# Codeshelf-0013_v00.net
KiCad netlist of a schematic drawn in EAGLE
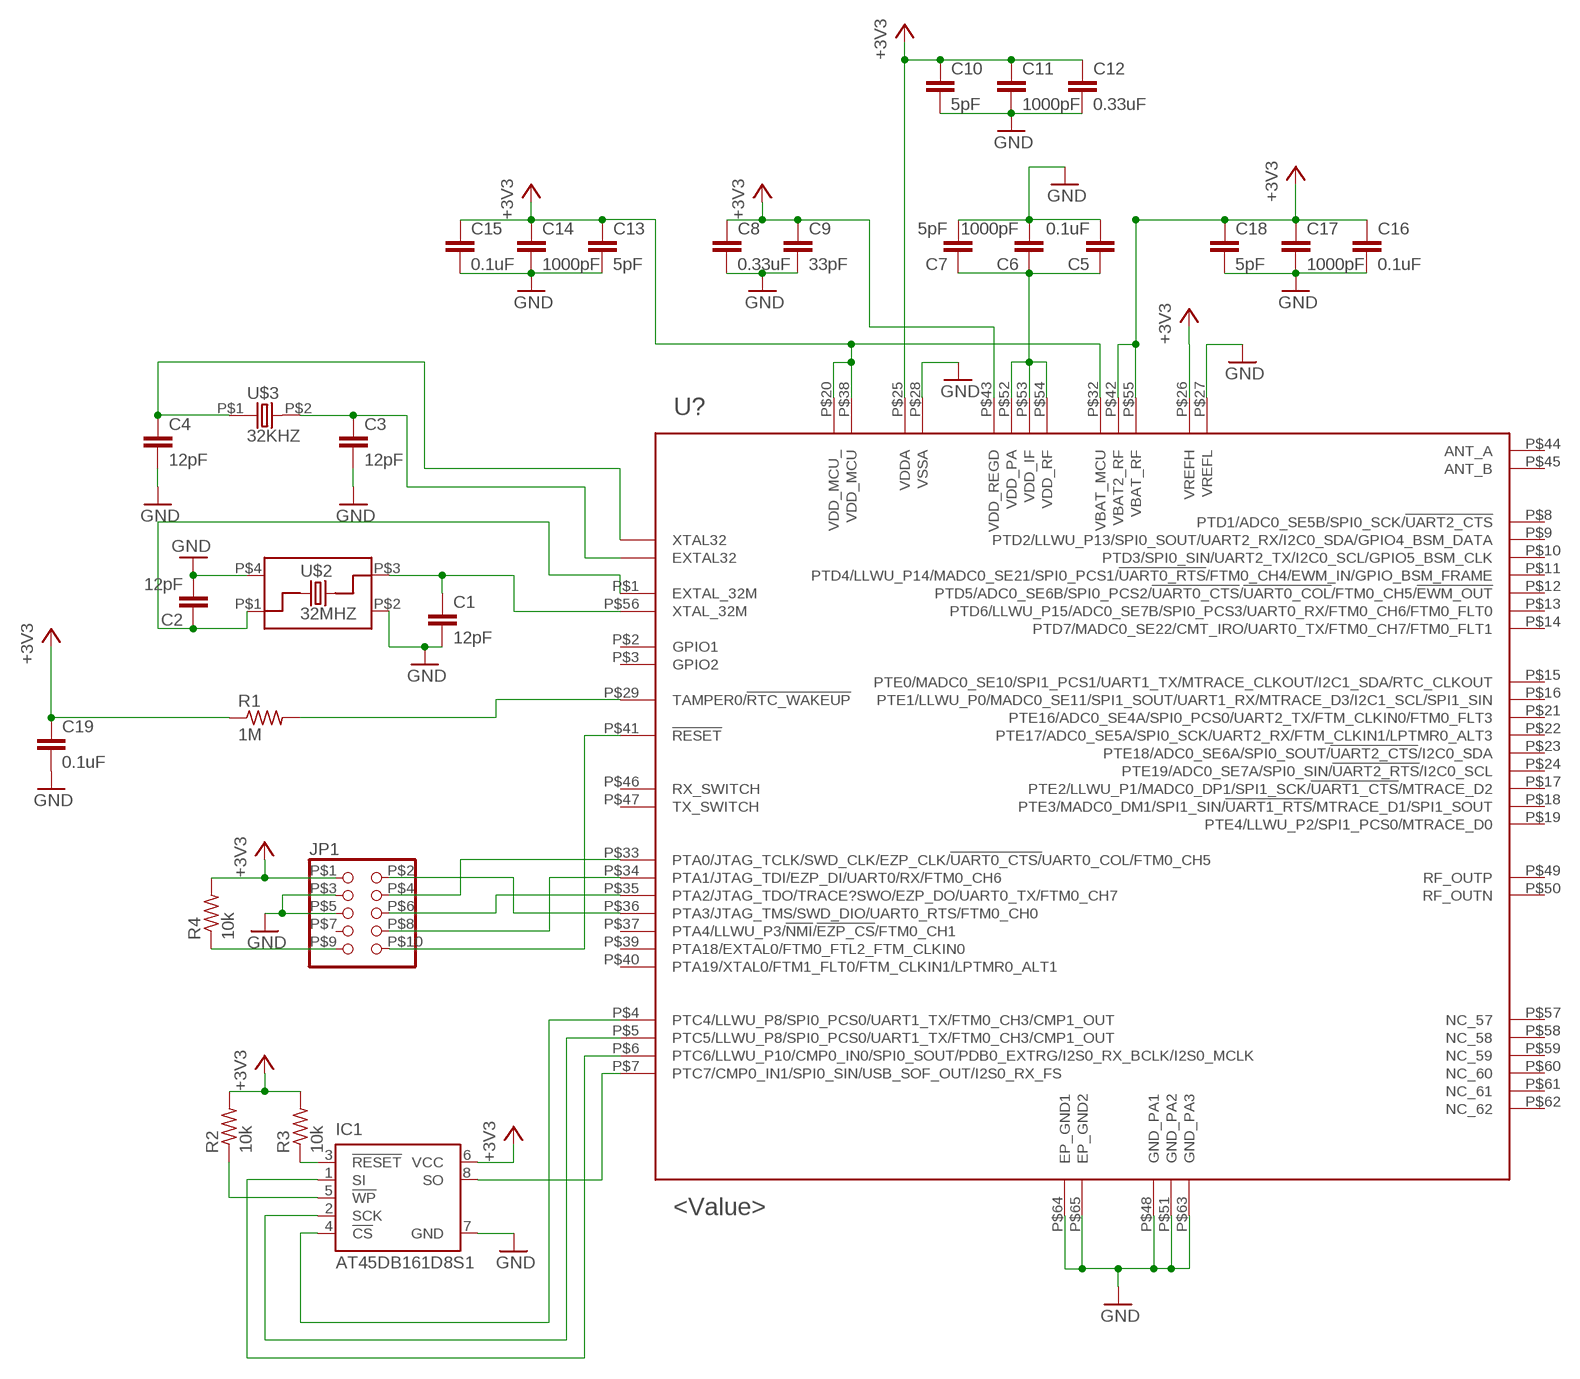
[diagram p0: schematic, sheet 1]

(export (version "E")
  (design (tool "Eeschema 10.0.6"))
  (components
    (comp (ref "C1")
      (value "12pF")
      (footprint "eagle-import:C0402")
      (libsource (lib "eagle-import") (part "RF-C0402"))
    )
    (comp (ref "C2")
      (value "12pF")
      (footprint "eagle-import:C0402")
      (libsource (lib "eagle-import") (part "RF-C0402"))
    )
    (comp (ref "C3")
      (value "12pF")
      (footprint "eagle-import:C0402")
      (libsource (lib "eagle-import") (part "RF-C0402"))
    )
    (comp (ref "C4")
      (value "12pF")
      (footprint "eagle-import:C0402")
      (libsource (lib "eagle-import") (part "RF-C0402"))
    )
    (comp (ref "C5")
      (value "0.1uF")
      (footprint "eagle-import:C0402")
      (libsource (lib "eagle-import") (part "RF-C0402"))
    )
    (comp (ref "C6")
      (value "1000pF")
      (footprint "eagle-import:C0402")
      (libsource (lib "eagle-import") (part "RF-C0402"))
    )
    (comp (ref "C7")
      (value "5pF")
      (footprint "eagle-import:C0402")
      (libsource (lib "eagle-import") (part "RF-C0402"))
    )
    (comp (ref "C8")
      (value "0.33uF")
      (footprint "eagle-import:C0402")
      (libsource (lib "eagle-import") (part "RF-C0402"))
    )
    (comp (ref "C9")
      (value "33pF")
      (footprint "eagle-import:C0402")
      (libsource (lib "eagle-import") (part "RF-C0402"))
    )
    (comp (ref "C10")
      (value "5pF")
      (footprint "eagle-import:C0402")
      (libsource (lib "eagle-import") (part "RF-C0402"))
    )
    (comp (ref "C11")
      (value "1000pF")
      (footprint "eagle-import:C0402")
      (libsource (lib "eagle-import") (part "RF-C0402"))
    )
    (comp (ref "C12")
      (value "0.33uF")
      (footprint "eagle-import:C0402")
      (libsource (lib "eagle-import") (part "RF-C0402"))
    )
    (comp (ref "C13")
      (value "5pF")
      (footprint "eagle-import:C0402")
      (libsource (lib "eagle-import") (part "RF-C0402"))
    )
    (comp (ref "C14")
      (value "1000pF")
      (footprint "eagle-import:C0402")
      (libsource (lib "eagle-import") (part "RF-C0402"))
    )
    (comp (ref "C15")
      (value "0.1uF")
      (footprint "eagle-import:C0402")
      (libsource (lib "eagle-import") (part "RF-C0402"))
    )
    (comp (ref "C16")
      (value "0.1uF")
      (footprint "eagle-import:C0402")
      (libsource (lib "eagle-import") (part "RF-C0402"))
    )
    (comp (ref "C17")
      (value "1000pF")
      (footprint "eagle-import:C0402")
      (libsource (lib "eagle-import") (part "RF-C0402"))
    )
    (comp (ref "C18")
      (value "5pF")
      (footprint "eagle-import:C0402")
      (libsource (lib "eagle-import") (part "RF-C0402"))
    )
    (comp (ref "C19")
      (value "0.1uF")
      (footprint "eagle-import:C0402")
      (libsource (lib "eagle-import") (part "RF-C0402"))
    )
    (comp (ref "IC1")
      (value "AT45DB161D8S1")
      (footprint "eagle-import:8S1")
      (libsource (lib "eagle-import") (part "AT45DB161D8S1"))
    )
    (comp (ref "JP1")
      (value "PINHD-2X5SMALL")
      (footprint "eagle-import:2X5HDR")
      (libsource (lib "eagle-import") (part "PINHD-2X5SMALL"))
    )
    (comp (ref "R1")
      (value "1M")
      (footprint "eagle-import:RF-R0402")
      (libsource (lib "eagle-import") (part "RF-R0402"))
    )
    (comp (ref "R2")
      (value "10k")
      (footprint "eagle-import:RF-R0402")
      (libsource (lib "eagle-import") (part "RF-R0402"))
    )
    (comp (ref "R3")
      (value "10k")
      (footprint "eagle-import:RF-R0402")
      (libsource (lib "eagle-import") (part "RF-R0402"))
    )
    (comp (ref "R4")
      (value "10k")
      (footprint "eagle-import:RF-R0402")
      (libsource (lib "eagle-import") (part "RF-R0402"))
    )
    (comp (ref "U$1")
      (value "MKW21D")
      (footprint "eagle-import:LGA63")
      (libsource (lib "eagle-import") (part "MKW21D"))
    )
    (comp (ref "U$2")
      (value "32MHZ")
      (footprint "eagle-import:32MHZSMD")
      (libsource (lib "eagle-import") (part "32MHZ"))
    )
    (comp (ref "U$3")
      (value "32KHZ")
      (footprint "eagle-import:32KHZSMD")
      (libsource (lib "eagle-import") (part "32KHZ"))
    )
  )
  (nets
    (net (code "1") (name "+3V3") (class "Default")
      (node (ref "C10") (pin "1") (pinfunction "1_1") (pintype "passive"))
      (node (ref "C11") (pin "1") (pinfunction "1_1") (pintype "passive"))
      (node (ref "C12") (pin "1") (pinfunction "1_1") (pintype "passive"))
      (node (ref "C13") (pin "1") (pinfunction "1_1") (pintype "passive"))
      (node (ref "C14") (pin "1") (pinfunction "1_1") (pintype "passive"))
      (node (ref "C15") (pin "1") (pinfunction "1_1") (pintype "passive"))
      (node (ref "C16") (pin "1") (pinfunction "1_1") (pintype "passive"))
      (node (ref "C17") (pin "1") (pinfunction "1_1") (pintype "passive"))
      (node (ref "C18") (pin "1") (pinfunction "1_1") (pintype "passive"))
      (node (ref "C19") (pin "1") (pinfunction "1_1") (pintype "passive"))
      (node (ref "C8") (pin "1") (pinfunction "1_1") (pintype "passive"))
      (node (ref "C9") (pin "1") (pinfunction "1_1") (pintype "passive"))
      (node (ref "IC1") (pin "6") (pinfunction "VCC_6") (pintype "power_in"))
      (node (ref "JP1") (pin "P$1") (pinfunction "1_P$1") (pintype "passive"))
      (node (ref "R1") (pin "1") (pinfunction "1_1") (pintype "passive"))
      (node (ref "R2") (pin "2") (pinfunction "2_2") (pintype "passive"))
      (node (ref "R3") (pin "2") (pinfunction "2_2") (pintype "passive"))
      (node (ref "R4") (pin "2") (pinfunction "2_2") (pintype "passive"))
      (node (ref "U$1") (pin "P$20") (pinfunction "VDD_MCU__P$20") (pintype "bidirectional"))
      (node (ref "U$1") (pin "P$25") (pinfunction "VDDA_P$25") (pintype "bidirectional"))
      (node (ref "U$1") (pin "P$26") (pinfunction "VREFH_P$26") (pintype "bidirectional"))
      (node (ref "U$1") (pin "P$32") (pinfunction "VBAT_MCU_P$32") (pintype "bidirectional"))
      (node (ref "U$1") (pin "P$38") (pinfunction "VDD_MCU_P$38") (pintype "bidirectional"))
      (node (ref "U$1") (pin "P$42") (pinfunction "VBAT2_RF_P$42") (pintype "bidirectional"))
      (node (ref "U$1") (pin "P$43") (pinfunction "VDD_REGD_P$43") (pintype "bidirectional"))
      (node (ref "U$1") (pin "P$55") (pinfunction "VBAT_RF_P$55") (pintype "bidirectional"))
    )
    (net (code "2") (name "GND") (class "Default")
      (node (ref "C1") (pin "2") (pinfunction "2_2") (pintype "passive"))
      (node (ref "C10") (pin "2") (pinfunction "2_2") (pintype "passive"))
      (node (ref "C11") (pin "2") (pinfunction "2_2") (pintype "passive"))
      (node (ref "C12") (pin "2") (pinfunction "2_2") (pintype "passive"))
      (node (ref "C13") (pin "2") (pinfunction "2_2") (pintype "passive"))
      (node (ref "C14") (pin "2") (pinfunction "2_2") (pintype "passive"))
      (node (ref "C15") (pin "2") (pinfunction "2_2") (pintype "passive"))
      (node (ref "C16") (pin "2") (pinfunction "2_2") (pintype "passive"))
      (node (ref "C17") (pin "2") (pinfunction "2_2") (pintype "passive"))
      (node (ref "C18") (pin "2") (pinfunction "2_2") (pintype "passive"))
      (node (ref "C19") (pin "2") (pinfunction "2_2") (pintype "passive"))
      (node (ref "C2") (pin "2") (pinfunction "2_2") (pintype "passive"))
      (node (ref "C3") (pin "2") (pinfunction "2_2") (pintype "passive"))
      (node (ref "C4") (pin "2") (pinfunction "2_2") (pintype "passive"))
      (node (ref "C5") (pin "2") (pinfunction "2_2") (pintype "passive"))
      (node (ref "C6") (pin "2") (pinfunction "2_2") (pintype "passive"))
      (node (ref "C7") (pin "2") (pinfunction "2_2") (pintype "passive"))
      (node (ref "C8") (pin "2") (pinfunction "2_2") (pintype "passive"))
      (node (ref "C9") (pin "2") (pinfunction "2_2") (pintype "passive"))
      (node (ref "IC1") (pin "7") (pinfunction "GND_7") (pintype "power_in"))
      (node (ref "JP1") (pin "P$3") (pinfunction "3_P$3") (pintype "passive"))
      (node (ref "JP1") (pin "P$5") (pinfunction "5_P$5") (pintype "passive"))
      (node (ref "U$1") (pin "P$27") (pinfunction "VREFL_P$27") (pintype "bidirectional"))
      (node (ref "U$1") (pin "P$28") (pinfunction "VSSA_P$28") (pintype "bidirectional"))
      (node (ref "U$1") (pin "P$48") (pinfunction "GND_PA1_P$48") (pintype "bidirectional"))
      (node (ref "U$1") (pin "P$51") (pinfunction "GND_PA2_P$51") (pintype "bidirectional"))
      (node (ref "U$1") (pin "P$63") (pinfunction "GND_PA3_P$63") (pintype "bidirectional"))
      (node (ref "U$1") (pin "P$64") (pinfunction "EP_GND1_P$64") (pintype "bidirectional"))
      (node (ref "U$1") (pin "P$65") (pinfunction "EP_GND2_P$65") (pintype "bidirectional"))
      (node (ref "U$2") (pin "P$2") (pinfunction "P$2_P$2") (pintype "power_in"))
      (node (ref "U$2") (pin "P$4") (pinfunction "P$4_P$4") (pintype "bidirectional"))
    )
    (net (code "3") (name "Net-(IC1-SCK)") (class "Default")
      (node (ref "IC1") (pin "2") (pinfunction "SCK_2") (pintype "input"))
      (node (ref "U$1") (pin "P$5") (pinfunction "PTC5/LLWU_P8/SPI0_PCS0/UART1_TX/FTM0_CH3/CMP1_OUT_P$5") (pintype "bidirectional"))
    )
    (net (code "4") (name "Net-(IC1-SI)") (class "Default")
      (node (ref "IC1") (pin "1") (pinfunction "SI_1") (pintype "input"))
      (node (ref "U$1") (pin "P$6") (pinfunction "PTC6/LLWU_P10/CMP0_IN0/SPI0_SOUT/PDB0_EXTRG/I2S0_RX_BCLK/I2S0_MCLK_P$6") (pintype "bidirectional"))
    )
    (net (code "5") (name "Net-(IC1-SO)") (class "Default")
      (node (ref "IC1") (pin "8") (pinfunction "SO_8") (pintype "output"))
      (node (ref "U$1") (pin "P$7") (pinfunction "PTC7/CMP0_IN1/SPI0_SIN/USB_SOF_OUT/I2S0_RX_FS_P$7") (pintype "bidirectional"))
    )
    (net (code "6") (name "Net-(IC1-~{CS})") (class "Default")
      (node (ref "IC1") (pin "4") (pinfunction "~{CS}_4") (pintype "input"))
      (node (ref "U$1") (pin "P$4") (pinfunction "PTC4/LLWU_P8/SPI0_PCS0/UART1_TX/FTM0_CH3/CMP1_OUT_P$4") (pintype "bidirectional"))
    )
    (net (code "7") (name "Net-(IC1-~{RESET})") (class "Default")
      (node (ref "IC1") (pin "3") (pinfunction "~{RESET}_3") (pintype "input"))
      (node (ref "R3") (pin "1") (pinfunction "1_1") (pintype "passive"))
    )
    (net (code "8") (name "Net-(IC1-~{WP})") (class "Default")
      (node (ref "IC1") (pin "5") (pinfunction "~{WP}_5") (pintype "input"))
      (node (ref "R2") (pin "1") (pinfunction "1_1") (pintype "passive"))
    )
    (net (code "9") (name "Net-(JP1-2)") (class "Default")
      (node (ref "JP1") (pin "P$2") (pinfunction "2_P$2") (pintype "passive"))
      (node (ref "U$1") (pin "P$36") (pinfunction "PTA3/JTAG_TMS/SWD_DIO/UART0_RTS/FTM0_CH0_P$36") (pintype "bidirectional"))
    )
    (net (code "10") (name "Net-(JP1-4)") (class "Default")
      (node (ref "JP1") (pin "P$4") (pinfunction "4_P$4") (pintype "passive"))
      (node (ref "U$1") (pin "P$33") (pinfunction "PTA0/JTAG_TCLK/SWD_CLK/EZP_CLK/~{UART0_CTS/}UART0_COL/FTM0_CH5_P$33") (pintype "bidirectional"))
    )
    (net (code "11") (name "Net-(JP1-6)") (class "Default")
      (node (ref "JP1") (pin "P$6") (pinfunction "6_P$6") (pintype "passive"))
      (node (ref "U$1") (pin "P$35") (pinfunction "PTA2/JTAG_TDO/TRACE?SWO/EZP_DO/UART0_TX/FTM0_CH7_P$35") (pintype "bidirectional"))
    )
    (net (code "12") (name "Net-(JP1-8)") (class "Default")
      (node (ref "JP1") (pin "P$8") (pinfunction "8_P$8") (pintype "passive"))
      (node (ref "U$1") (pin "P$34") (pinfunction "PTA1/JTAG_TDI/EZP_DI/UART0/RX/FTM0_CH6_P$34") (pintype "bidirectional"))
    )
    (net (code "13") (name "Net-(JP1-9)") (class "Default")
      (node (ref "JP1") (pin "P$9") (pinfunction "9_P$9") (pintype "passive"))
      (node (ref "R4") (pin "1") (pinfunction "1_1") (pintype "passive"))
    )
    (net (code "14") (name "Net-(JP1-10)") (class "Default")
      (node (ref "JP1") (pin "P$10") (pinfunction "10_P$10") (pintype "passive"))
      (node (ref "U$1") (pin "P$41") (pinfunction "~{RESET}_P$41") (pintype "bidirectional"))
    )
    (net (code "15") (name "Net-(U$1-EXTAL32)") (class "Default")
      (node (ref "C3") (pin "1") (pinfunction "1_1") (pintype "passive"))
      (node (ref "U$1") (pin "P$31") (pinfunction "EXTAL32_P$31") (pintype "bidirectional"))
      (node (ref "U$3") (pin "P$2") (pinfunction "2_P$2") (pintype "passive"))
    )
    (net (code "16") (name "Net-(U$1-EXTAL_32M)") (class "Default")
      (node (ref "C2") (pin "1") (pinfunction "1_1") (pintype "passive"))
      (node (ref "U$1") (pin "P$1") (pinfunction "EXTAL_32M_P$1") (pintype "bidirectional"))
      (node (ref "U$2") (pin "P$1") (pinfunction "P$1_P$1") (pintype "passive"))
    )
    (net (code "17") (name "Net-(U$1-TAMPER0{slash}~{RTC_WAKEUP})") (class "Default")
      (node (ref "R1") (pin "2") (pinfunction "2_2") (pintype "passive"))
      (node (ref "U$1") (pin "P$29") (pinfunction "TAMPER0/~{RTC_WAKEUP}_P$29") (pintype "bidirectional"))
    )
    (net (code "18") (name "Net-(U$1-VDD_IF)") (class "Default")
      (node (ref "C5") (pin "1") (pinfunction "1_1") (pintype "passive"))
      (node (ref "C6") (pin "1") (pinfunction "1_1") (pintype "passive"))
      (node (ref "C7") (pin "1") (pinfunction "1_1") (pintype "passive"))
      (node (ref "U$1") (pin "P$52") (pinfunction "VDD_PA_P$52") (pintype "bidirectional"))
      (node (ref "U$1") (pin "P$53") (pinfunction "VDD_IF_P$53") (pintype "bidirectional"))
      (node (ref "U$1") (pin "P$54") (pinfunction "VDD_RF_P$54") (pintype "bidirectional"))
    )
    (net (code "19") (name "Net-(U$1-XTAL32)") (class "Default")
      (node (ref "C4") (pin "1") (pinfunction "1_1") (pintype "passive"))
      (node (ref "U$1") (pin "P$30") (pinfunction "XTAL32_P$30") (pintype "bidirectional"))
      (node (ref "U$3") (pin "P$1") (pinfunction "1_P$1") (pintype "passive"))
    )
    (net (code "20") (name "Net-(U$1-XTAL_32M)") (class "Default")
      (node (ref "C1") (pin "1") (pinfunction "1_1") (pintype "passive"))
      (node (ref "U$1") (pin "P$56") (pinfunction "XTAL_32M_P$56") (pintype "bidirectional"))
      (node (ref "U$2") (pin "P$3") (pinfunction "P$3_P$3") (pintype "passive"))
    )
    (net (code "21") (name "unconnected-(JP1-7-PadP$7)") (class "Default")
      (node (ref "JP1") (pin "P$7") (pinfunction "7_P$7") (pintype "passive"))
    )
    (net (code "22") (name "unconnected-(U$1-ANT_A-PadP$44)") (class "Default")
      (node (ref "U$1") (pin "P$44") (pinfunction "ANT_A_P$44") (pintype "bidirectional"))
    )
    (net (code "23") (name "unconnected-(U$1-ANT_B-PadP$45)") (class "Default")
      (node (ref "U$1") (pin "P$45") (pinfunction "ANT_B_P$45") (pintype "bidirectional"))
    )
    (net (code "24") (name "unconnected-(U$1-GPIO1-PadP$2)") (class "Default")
      (node (ref "U$1") (pin "P$2") (pinfunction "GPIO1_P$2") (pintype "bidirectional"))
    )
    (net (code "25") (name "unconnected-(U$1-GPIO2-PadP$3)") (class "Default")
      (node (ref "U$1") (pin "P$3") (pinfunction "GPIO2_P$3") (pintype "bidirectional"))
    )
    (net (code "26") (name "unconnected-(U$1-NC_57-PadP$57)") (class "Default")
      (node (ref "U$1") (pin "P$57") (pinfunction "NC_57_P$57") (pintype "bidirectional"))
    )
    (net (code "27") (name "unconnected-(U$1-NC_58-PadP$58)") (class "Default")
      (node (ref "U$1") (pin "P$58") (pinfunction "NC_58_P$58") (pintype "bidirectional"))
    )
    (net (code "28") (name "unconnected-(U$1-NC_59-PadP$59)") (class "Default")
      (node (ref "U$1") (pin "P$59") (pinfunction "NC_59_P$59") (pintype "bidirectional"))
    )
    (net (code "29") (name "unconnected-(U$1-NC_60-PadP$60)") (class "Default")
      (node (ref "U$1") (pin "P$60") (pinfunction "NC_60_P$60") (pintype "bidirectional"))
    )
    (net (code "30") (name "unconnected-(U$1-NC_61-PadP$61)") (class "Default")
      (node (ref "U$1") (pin "P$61") (pinfunction "NC_61_P$61") (pintype "bidirectional"))
    )
    (net (code "31") (name "unconnected-(U$1-NC_62-PadP$62)") (class "Default")
      (node (ref "U$1") (pin "P$62") (pinfunction "NC_62_P$62") (pintype "bidirectional"))
    )
    (net (code "32") (name "unconnected-(U$1-PTA4{slash}LLWU_P3{slash}~{NMI}{slash}~{EZP_CS}{slash}FTM0_CH1-PadP$37)") (class "Default")
      (node (ref "U$1") (pin "P$37") (pinfunction "PTA4/LLWU_P3/~{NMI}/~{EZP_CS}/FTM0_CH1_P$37") (pintype "bidirectional"))
    )
    (net (code "33") (name "unconnected-(U$1-PTA18{slash}EXTAL0{slash}FTM0_FTL2_FTM_CLKIN0-PadP$39)") (class "Default")
      (node (ref "U$1") (pin "P$39") (pinfunction "PTA18/EXTAL0/FTM0_FTL2_FTM_CLKIN0_P$39") (pintype "bidirectional"))
    )
    (net (code "34") (name "unconnected-(U$1-PTA19{slash}XTAL0{slash}FTM1_FLT0{slash}FTM_CLKIN1{slash}LPTMR0_ALT1-PadP$40)") (class "Default")
      (node (ref "U$1") (pin "P$40") (pinfunction "PTA19/XTAL0/FTM1_FLT0/FTM_CLKIN1/LPTMR0_ALT1_P$40") (pintype "bidirectional"))
    )
    (net (code "35") (name "unconnected-(U$1-PTD1{slash}ADC0_SE5B{slash}SPI0_SCK{slash}~{UART2_CTS}-PadP$8)") (class "Default")
      (node (ref "U$1") (pin "P$8") (pinfunction "PTD1/ADC0_SE5B/SPI0_SCK/~{UART2_CTS}_P$8") (pintype "bidirectional"))
    )
    (net (code "36") (name "unconnected-(U$1-PTD2{slash}LLWU_P13{slash}SPI0_SOUT{slash}UART2_RX{slash}I2C0_SDA{slash}GPIO4_BSM_DATA-PadP$9)") (class "Default")
      (node (ref "U$1") (pin "P$9") (pinfunction "PTD2/LLWU_P13/SPI0_SOUT/UART2_RX/I2C0_SDA/GPIO4_BSM_DATA_P$9") (pintype "bidirectional"))
    )
    (net (code "37") (name "unconnected-(U$1-PTD3{slash}SPI0_SIN{slash}UART2_TX{slash}I2C0_SCL{slash}GPIO5_BSM_CLK-PadP$10)") (class "Default")
      (node (ref "U$1") (pin "P$10") (pinfunction "PTD3/SPI0_SIN/UART2_TX/I2C0_SCL/GPIO5_BSM_CLK_P$10") (pintype "bidirectional"))
    )
    (net (code "38") (name "unconnected-(U$1-PTD4{slash}LLWU_P14{slash}MADC0_SE21{slash}SPI0_PCS1{slash}~{UART0_RTS}{slash}FTM0_CH4{slash}EWM_IN{slash}GPIO_BSM_FRAME-PadP$11)") (class "Default")
      (node (ref "U$1") (pin "P$11") (pinfunction "PTD4/LLWU_P14/MADC0_SE21/SPI0_PCS1/~{UART0_RTS}/FTM0_CH4/EWM_IN/GPIO_BSM_FRAME_P$11") (pintype "bidirectional"))
    )
    (net (code "39") (name "unconnected-(U$1-PTD5{slash}ADC0_SE6B{slash}SPI0_PCS2{slash}~{UART0_CTS}{slash}~{UART0_COL}{slash}FTM0_CH5{slash}~{EWM_OUT}-PadP$12)") (class "Default")
      (node (ref "U$1") (pin "P$12") (pinfunction "PTD5/ADC0_SE6B/SPI0_PCS2/~{UART0_CTS}/~{UART0_COL}/FTM0_CH5/~{EWM_OUT}_P$12") (pintype "bidirectional"))
    )
    (net (code "40") (name "unconnected-(U$1-PTD6{slash}LLWU_P15{slash}ADC0_SE7B{slash}SPI0_PCS3{slash}UART0_RX{slash}FTM0_CH6{slash}FTM0_FLT0-PadP$13)") (class "Default")
      (node (ref "U$1") (pin "P$13") (pinfunction "PTD6/LLWU_P15/ADC0_SE7B/SPI0_PCS3/UART0_RX/FTM0_CH6/FTM0_FLT0_P$13") (pintype "bidirectional"))
    )
    (net (code "41") (name "unconnected-(U$1-PTD7{slash}MADC0_SE22{slash}CMT_IRO{slash}UART0_TX{slash}FTM0_CH7{slash}FTM0_FLT1-PadP$14)") (class "Default")
      (node (ref "U$1") (pin "P$14") (pinfunction "PTD7/MADC0_SE22/CMT_IRO/UART0_TX/FTM0_CH7/FTM0_FLT1_P$14") (pintype "bidirectional"))
    )
    (net (code "42") (name "unconnected-(U$1-PTE0{slash}MADC0_SE10{slash}SPI1_PCS1{slash}UART1_TX{slash}MTRACE_CLKOUT{slash}I2C1_SDA{slash}RTC_CLKOUT-PadP$15)") (class "Default")
      (node (ref "U$1") (pin "P$15") (pinfunction "PTE0/MADC0_SE10/SPI1_PCS1/UART1_TX/MTRACE_CLKOUT/I2C1_SDA/RTC_CLKOUT_P$15") (pintype "bidirectional"))
    )
    (net (code "43") (name "unconnected-(U$1-PTE1{slash}LLWU_P0{slash}MADC0_SE11{slash}SPI1_SOUT{slash}UART1_RX{slash}MTRACE_D3{slash}I2C1_SCL{slash}SPI1_SIN-PadP$16)") (class "Default")
      (node (ref "U$1") (pin "P$16") (pinfunction "PTE1/LLWU_P0/MADC0_SE11/SPI1_SOUT/UART1_RX/MTRACE_D3/I2C1_SCL/SPI1_SIN_P$16") (pintype "bidirectional"))
    )
    (net (code "44") (name "unconnected-(U$1-PTE2{slash}LLWU_P1{slash}MADC0_DP1{slash}SPI1_SCK{slash}~{UART1_CTS}{slash}MTRACE_D2-PadP$17)") (class "Default")
      (node (ref "U$1") (pin "P$17") (pinfunction "PTE2/LLWU_P1/MADC0_DP1/SPI1_SCK/~{UART1_CTS}/MTRACE_D2_P$17") (pintype "bidirectional"))
    )
    (net (code "45") (name "unconnected-(U$1-PTE3{slash}MADC0_DM1{slash}SPI1_SIN{slash}~{UART1_RTS}{slash}MTRACE_D1{slash}SPI1_SOUT-PadP$18)") (class "Default")
      (node (ref "U$1") (pin "P$18") (pinfunction "PTE3/MADC0_DM1/SPI1_SIN/~{UART1_RTS}/MTRACE_D1/SPI1_SOUT_P$18") (pintype "bidirectional"))
    )
    (net (code "46") (name "unconnected-(U$1-PTE4{slash}LLWU_P2{slash}SPI1_PCS0{slash}MTRACE_D0-PadP$19)") (class "Default")
      (node (ref "U$1") (pin "P$19") (pinfunction "PTE4/LLWU_P2/SPI1_PCS0/MTRACE_D0_P$19") (pintype "bidirectional"))
    )
    (net (code "47") (name "unconnected-(U$1-PTE16{slash}ADC0_SE4A{slash}SPI0_PCS0{slash}UART2_TX{slash}FTM_CLKIN0{slash}FTM0_FLT3-PadP$21)") (class "Default")
      (node (ref "U$1") (pin "P$21") (pinfunction "PTE16/ADC0_SE4A/SPI0_PCS0/UART2_TX/FTM_CLKIN0/FTM0_FLT3_P$21") (pintype "bidirectional"))
    )
    (net (code "48") (name "unconnected-(U$1-PTE17{slash}ADC0_SE5A{slash}SPI0_SCK{slash}UART2_RX{slash}FTM_CLKIN1{slash}LPTMR0_ALT3-PadP$22)") (class "Default")
      (node (ref "U$1") (pin "P$22") (pinfunction "PTE17/ADC0_SE5A/SPI0_SCK/UART2_RX/FTM_CLKIN1/LPTMR0_ALT3_P$22") (pintype "bidirectional"))
    )
    (net (code "49") (name "unconnected-(U$1-PTE18{slash}ADC0_SE6A{slash}SPI0_SOUT{slash}~{UART2_CTS}{slash}I2C0_SDA-PadP$23)") (class "Default")
      (node (ref "U$1") (pin "P$23") (pinfunction "PTE18/ADC0_SE6A/SPI0_SOUT/~{UART2_CTS}/I2C0_SDA_P$23") (pintype "bidirectional"))
    )
    (net (code "50") (name "unconnected-(U$1-PTE19{slash}ADC0_SE7A{slash}SPI0_SIN{slash}~{UART2_RTS}{slash}I2C0_SCL-PadP$24)") (class "Default")
      (node (ref "U$1") (pin "P$24") (pinfunction "PTE19/ADC0_SE7A/SPI0_SIN/~{UART2_RTS}/I2C0_SCL_P$24") (pintype "bidirectional"))
    )
    (net (code "51") (name "unconnected-(U$1-RF_OUTN-PadP$50)") (class "Default")
      (node (ref "U$1") (pin "P$50") (pinfunction "RF_OUTN_P$50") (pintype "bidirectional"))
    )
    (net (code "52") (name "unconnected-(U$1-RF_OUTP-PadP$49)") (class "Default")
      (node (ref "U$1") (pin "P$49") (pinfunction "RF_OUTP_P$49") (pintype "bidirectional"))
    )
    (net (code "53") (name "unconnected-(U$1-RX_SWITCH-PadP$46)") (class "Default")
      (node (ref "U$1") (pin "P$46") (pinfunction "RX_SWITCH_P$46") (pintype "bidirectional"))
    )
    (net (code "54") (name "unconnected-(U$1-TX_SWITCH-PadP$47)") (class "Default")
      (node (ref "U$1") (pin "P$47") (pinfunction "TX_SWITCH_P$47") (pintype "bidirectional"))
    )
  )
)
